# CW308T_XMEGA_MICRO.net
KiCad netlist of a schematic drawn in Altium Designer
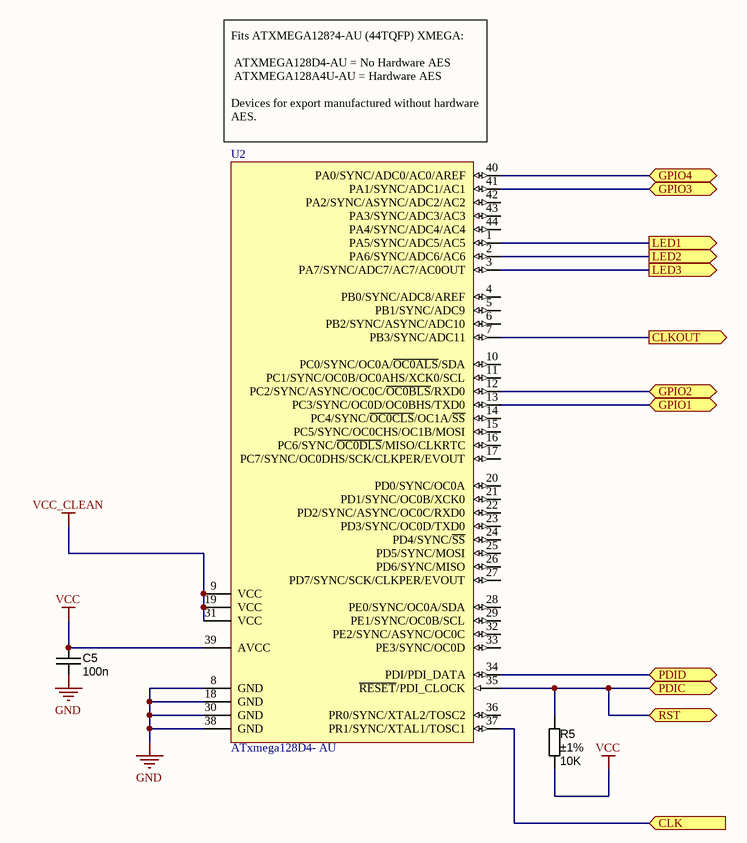
[diagram p0: CW308T_XMEGA_MICRO.SchDoc]

(export (version "E")
  (design (tool "Eeschema 10.0.6"))
  (components
    (comp (ref "C5")
      (value "100n")
      (footprint "CAPC1608X90N")
      (description "Capacitor SMD Cer 100nF 10% 50V X7R 0603")
      (fields (field (name "TOLERANCE") "±10%") (field (name "Comment") "approved sub OK"))
      (libsource (lib "PBL - Capacitors") (part "CAPC_100n_0603_X7R_50V_10%"))
    )
    (comp (ref "R5")
      (value "10K")
      (footprint "RESC1608X55N")
      (description "Resistor SMD chip 10k Ohm 0.1W 1% 0603")
      (fields (field (name "TOLERANCE") "±1%") (field (name "Comment") "Thick Film"))
      (libsource (lib "PBL - Resistors") (part "RES_10K_0603_1%"))
    )
    (comp (ref "U2")
      (value "ATxmega128D4- AU")
      (footprint "44A_M")
      (fields (field (name "MANUFACTURER") "Atmel"))
      (libsource (lib "Altium Content Vault") (part "MC-8B-ATXM16D4-SQ44"))
    )
  )
  (nets
    (net (code "1") (name "/CLK") (class "Default")
      (node (ref "U2") (pin "37") (pinfunction "PR1/SYNC/XTAL1/TOSC1_37") (pintype "bidirectional"))
    )
    (net (code "2") (name "/CLKOUT") (class "Default")
      (node (ref "U2") (pin "7") (pinfunction "PB3/SYNC/ADC11_7") (pintype "bidirectional"))
    )
    (net (code "3") (name "/GPIO1") (class "Default")
      (node (ref "U2") (pin "13") (pinfunction "PC3/SYNC/OC0D/OC0BHS/TXD0_13") (pintype "bidirectional"))
    )
    (net (code "4") (name "/GPIO2") (class "Default")
      (node (ref "U2") (pin "12") (pinfunction "PC2/SYNC/ASYNC/OC0C/~{OC0BLS}/RXD0_12") (pintype "bidirectional"))
    )
    (net (code "5") (name "/GPIO3") (class "Default")
      (node (ref "U2") (pin "41") (pinfunction "PA1/SYNC/ADC1/AC1_41") (pintype "bidirectional"))
    )
    (net (code "6") (name "/GPIO4") (class "Default")
      (node (ref "U2") (pin "40") (pinfunction "PA0/SYNC/ADC0/AC0/AREF_40") (pintype "bidirectional"))
    )
    (net (code "7") (name "/LED1") (class "Default")
      (node (ref "U2") (pin "1") (pinfunction "PA5/SYNC/ADC5/AC5_1") (pintype "bidirectional"))
    )
    (net (code "8") (name "/LED2") (class "Default")
      (node (ref "U2") (pin "2") (pinfunction "PA6/SYNC/ADC6/AC6_2") (pintype "bidirectional"))
    )
    (net (code "9") (name "/LED3") (class "Default")
      (node (ref "U2") (pin "3") (pinfunction "PA7/SYNC/ADC7/AC7/AC0OUT_3") (pintype "bidirectional"))
    )
    (net (code "10") (name "/PDIC") (class "Default")
      (node (ref "R5") (pin "2") (pinfunction "2_2") (pintype "passive"))
      (node (ref "U2") (pin "35") (pinfunction "~{RESET}/PDI_CLOCK_35") (pintype "input"))
    )
    (net (code "11") (name "/PDID") (class "Default")
      (node (ref "U2") (pin "34") (pinfunction "PDI/PDI_DATA_34") (pintype "bidirectional"))
    )
    (net (code "12") (name "GND") (class "Default")
      (node (ref "C5") (pin "2") (pintype "passive"))
      (node (ref "U2") (pin "18") (pinfunction "GND_18") (pintype "power_in"))
      (node (ref "U2") (pin "30") (pinfunction "GND_30") (pintype "power_in"))
      (node (ref "U2") (pin "38") (pinfunction "GND_38") (pintype "power_in"))
      (node (ref "U2") (pin "8") (pinfunction "GND_8") (pintype "power_in"))
    )
    (net (code "13") (name "VCC") (class "Default")
      (node (ref "C5") (pin "1") (pintype "passive"))
      (node (ref "R5") (pin "1") (pinfunction "1_1") (pintype "passive"))
      (node (ref "U2") (pin "39") (pinfunction "AVCC_39") (pintype "power_in"))
    )
    (net (code "14") (name "VCC_CLEAN") (class "Default")
      (node (ref "U2") (pin "19") (pinfunction "VCC_19") (pintype "power_in"))
      (node (ref "U2") (pin "31") (pinfunction "VCC_31") (pintype "power_in"))
      (node (ref "U2") (pin "9") (pinfunction "VCC_9") (pintype "power_in"))
    )
    (net (code "15") (name "unconnected-(U2-PA2{slash}SYNC{slash}ASYNC{slash}ADC2{slash}AC2-Pad42)") (class "Default")
      (node (ref "U2") (pin "42") (pinfunction "PA2/SYNC/ASYNC/ADC2/AC2_42") (pintype "bidirectional"))
    )
    (net (code "16") (name "unconnected-(U2-PA3{slash}SYNC{slash}ADC3{slash}AC3-Pad43)") (class "Default")
      (node (ref "U2") (pin "43") (pinfunction "PA3/SYNC/ADC3/AC3_43") (pintype "bidirectional"))
    )
    (net (code "17") (name "unconnected-(U2-PA4{slash}SYNC{slash}ADC4{slash}AC4-Pad44)") (class "Default")
      (node (ref "U2") (pin "44") (pinfunction "PA4/SYNC/ADC4/AC4_44") (pintype "bidirectional"))
    )
    (net (code "18") (name "unconnected-(U2-PB0{slash}SYNC{slash}ADC8{slash}AREF-Pad4)") (class "Default")
      (node (ref "U2") (pin "4") (pinfunction "PB0/SYNC/ADC8/AREF_4") (pintype "bidirectional"))
    )
    (net (code "19") (name "unconnected-(U2-PB1{slash}SYNC{slash}ADC9-Pad5)") (class "Default")
      (node (ref "U2") (pin "5") (pinfunction "PB1/SYNC/ADC9_5") (pintype "bidirectional"))
    )
    (net (code "20") (name "unconnected-(U2-PB2{slash}SYNC{slash}ASYNC{slash}ADC10-Pad6)") (class "Default")
      (node (ref "U2") (pin "6") (pinfunction "PB2/SYNC/ASYNC/ADC10_6") (pintype "bidirectional"))
    )
    (net (code "21") (name "unconnected-(U2-PC0{slash}SYNC{slash}OC0A{slash}~{OC0ALS}{slash}SDA-Pad10)") (class "Default")
      (node (ref "U2") (pin "10") (pinfunction "PC0/SYNC/OC0A/~{OC0ALS}/SDA_10") (pintype "bidirectional"))
    )
    (net (code "22") (name "unconnected-(U2-PC1{slash}SYNC{slash}OC0B{slash}OC0AHS{slash}XCK0{slash}SCL-Pad11)") (class "Default")
      (node (ref "U2") (pin "11") (pinfunction "PC1/SYNC/OC0B/OC0AHS/XCK0/SCL_11") (pintype "bidirectional"))
    )
    (net (code "23") (name "unconnected-(U2-PC4{slash}SYNC{slash}~{OC0CLS}{slash}OC1A{slash}~{SS}-Pad14)") (class "Default")
      (node (ref "U2") (pin "14") (pinfunction "PC4/SYNC/~{OC0CLS}/OC1A/~{SS}_14") (pintype "bidirectional"))
    )
    (net (code "24") (name "unconnected-(U2-PC5{slash}SYNC{slash}OC0CHS{slash}OC1B{slash}MOSI-Pad15)") (class "Default")
      (node (ref "U2") (pin "15") (pinfunction "PC5/SYNC/OC0CHS/OC1B/MOSI_15") (pintype "bidirectional"))
    )
    (net (code "25") (name "unconnected-(U2-PC6{slash}SYNC{slash}~{OC0DLS}{slash}MISO{slash}CLKRTC-Pad16)") (class "Default")
      (node (ref "U2") (pin "16") (pinfunction "PC6/SYNC/~{OC0DLS}/MISO/CLKRTC_16") (pintype "bidirectional"))
    )
    (net (code "26") (name "unconnected-(U2-PC7{slash}SYNC{slash}OC0DHS{slash}SCK{slash}CLKPER{slash}EVOUT-Pad17)") (class "Default")
      (node (ref "U2") (pin "17") (pinfunction "PC7/SYNC/OC0DHS/SCK/CLKPER/EVOUT_17") (pintype "bidirectional"))
    )
    (net (code "27") (name "unconnected-(U2-PD0{slash}SYNC{slash}OC0A-Pad20)") (class "Default")
      (node (ref "U2") (pin "20") (pinfunction "PD0/SYNC/OC0A_20") (pintype "bidirectional"))
    )
    (net (code "28") (name "unconnected-(U2-PD1{slash}SYNC{slash}OC0B{slash}XCK0-Pad21)") (class "Default")
      (node (ref "U2") (pin "21") (pinfunction "PD1/SYNC/OC0B/XCK0_21") (pintype "bidirectional"))
    )
    (net (code "29") (name "unconnected-(U2-PD2{slash}SYNC{slash}ASYNC{slash}OC0C{slash}RXD0-Pad22)") (class "Default")
      (node (ref "U2") (pin "22") (pinfunction "PD2/SYNC/ASYNC/OC0C/RXD0_22") (pintype "bidirectional"))
    )
    (net (code "30") (name "unconnected-(U2-PD3{slash}SYNC{slash}OC0D{slash}TXD0-Pad23)") (class "Default")
      (node (ref "U2") (pin "23") (pinfunction "PD3/SYNC/OC0D/TXD0_23") (pintype "bidirectional"))
    )
    (net (code "31") (name "unconnected-(U2-PD4{slash}SYNC{slash}~{SS}-Pad24)") (class "Default")
      (node (ref "U2") (pin "24") (pinfunction "PD4/SYNC/~{SS}_24") (pintype "bidirectional"))
    )
    (net (code "32") (name "unconnected-(U2-PD5{slash}SYNC{slash}MOSI-Pad25)") (class "Default")
      (node (ref "U2") (pin "25") (pinfunction "PD5/SYNC/MOSI_25") (pintype "bidirectional"))
    )
    (net (code "33") (name "unconnected-(U2-PD6{slash}SYNC{slash}MISO-Pad26)") (class "Default")
      (node (ref "U2") (pin "26") (pinfunction "PD6/SYNC/MISO_26") (pintype "bidirectional"))
    )
    (net (code "34") (name "unconnected-(U2-PD7{slash}SYNC{slash}SCK{slash}CLKPER{slash}EVOUT-Pad27)") (class "Default")
      (node (ref "U2") (pin "27") (pinfunction "PD7/SYNC/SCK/CLKPER/EVOUT_27") (pintype "bidirectional"))
    )
    (net (code "35") (name "unconnected-(U2-PE0{slash}SYNC{slash}OC0A{slash}SDA-Pad28)") (class "Default")
      (node (ref "U2") (pin "28") (pinfunction "PE0/SYNC/OC0A/SDA_28") (pintype "bidirectional"))
    )
    (net (code "36") (name "unconnected-(U2-PE1{slash}SYNC{slash}OC0B{slash}SCL-Pad29)") (class "Default")
      (node (ref "U2") (pin "29") (pinfunction "PE1/SYNC/OC0B/SCL_29") (pintype "bidirectional"))
    )
    (net (code "37") (name "unconnected-(U2-PE2{slash}SYNC{slash}ASYNC{slash}OC0C-Pad32)") (class "Default")
      (node (ref "U2") (pin "32") (pinfunction "PE2/SYNC/ASYNC/OC0C_32") (pintype "bidirectional"))
    )
    (net (code "38") (name "unconnected-(U2-PE3{slash}SYNC{slash}OC0D-Pad33)") (class "Default")
      (node (ref "U2") (pin "33") (pinfunction "PE3/SYNC/OC0D_33") (pintype "bidirectional"))
    )
    (net (code "39") (name "unconnected-(U2-PR0{slash}SYNC{slash}XTAL2{slash}TOSC2-Pad36)") (class "Default")
      (node (ref "U2") (pin "36") (pinfunction "PR0/SYNC/XTAL2/TOSC2_36") (pintype "bidirectional"))
    )
  )
)
